# Juice_Rescue_v1_0.net
KiCad netlist of a schematic drawn in EAGLE
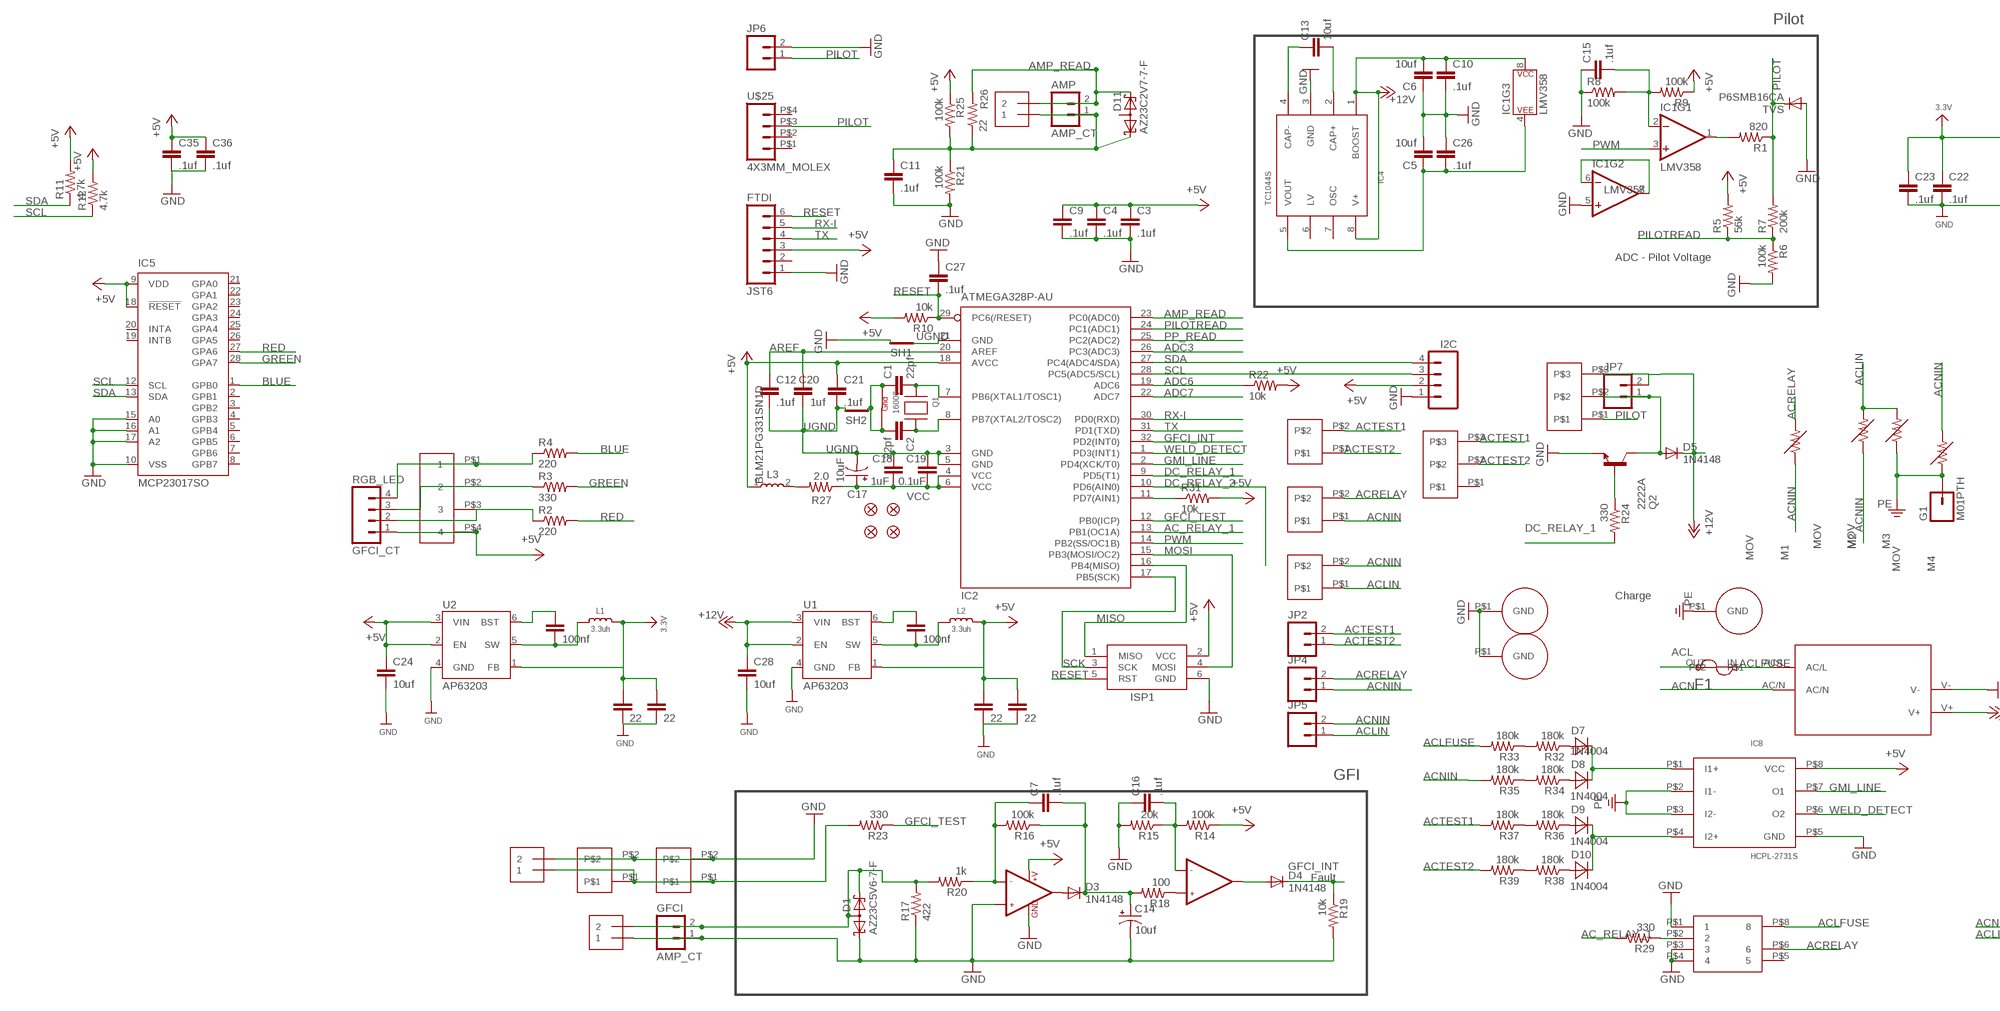
[diagram p0: schematic, sheet 1, part 1 of 2]
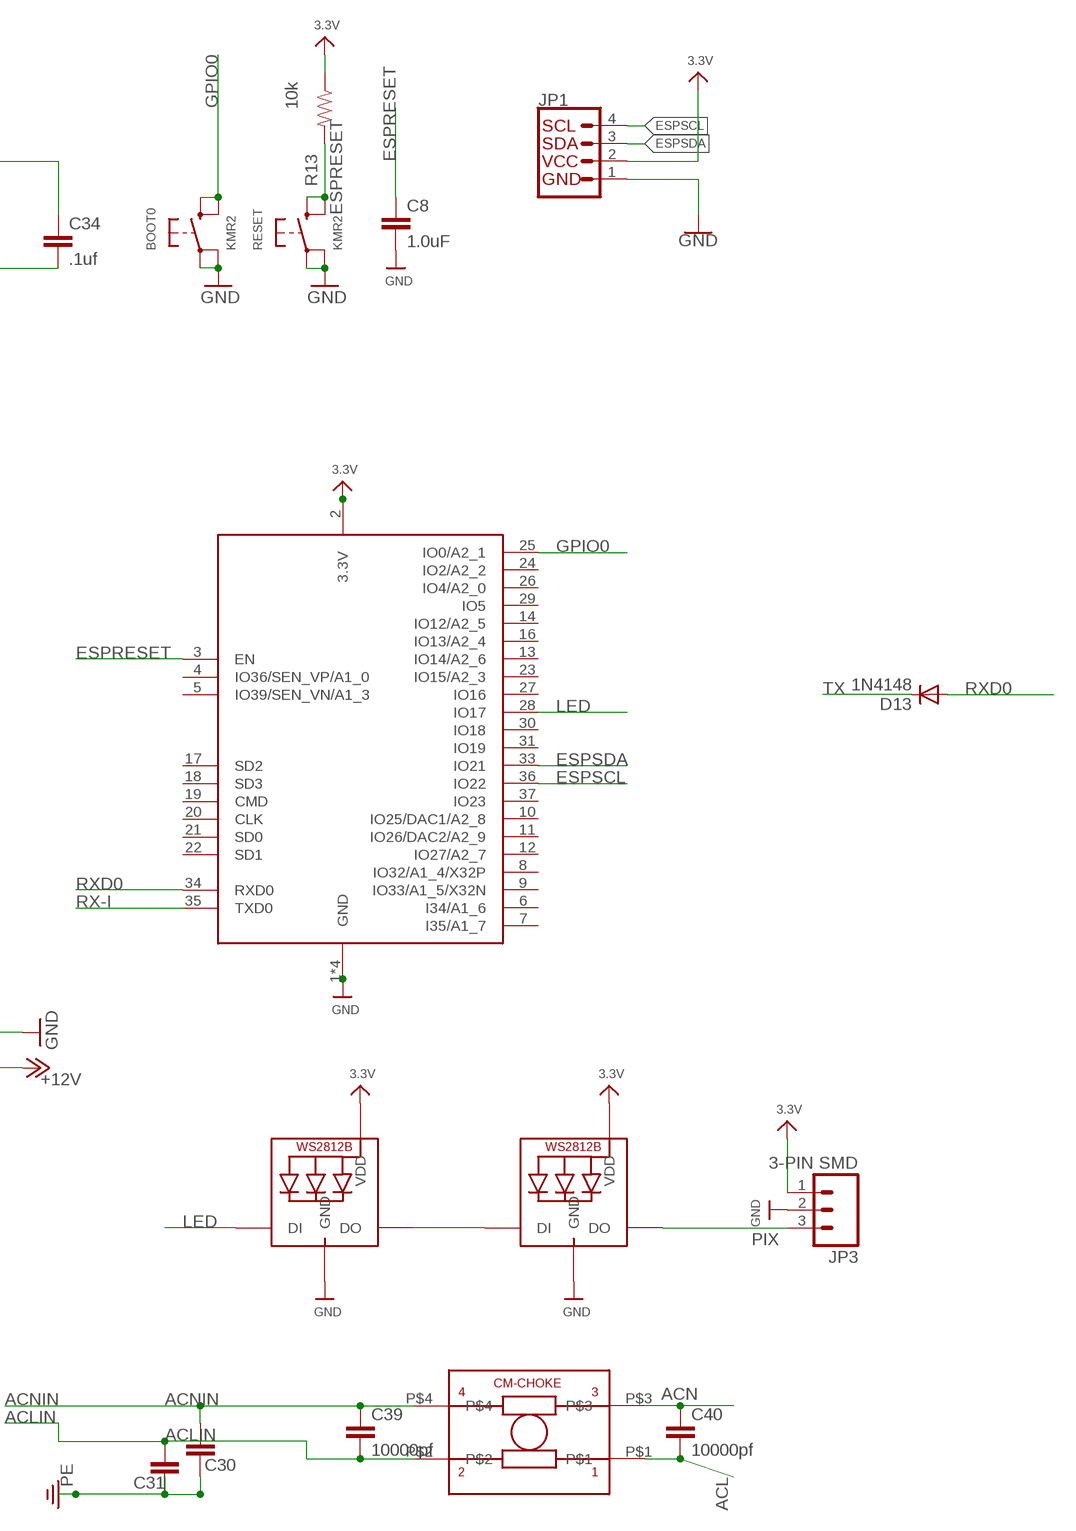
[diagram p1: schematic, sheet 1, part 2 of 2]

(export (version "E")
  (design (tool "Eeschema 10.0.6"))
  (components
    (comp (ref "AMP")
      (value "AMP_CT")
      (footprint "eagle-import:MOLEX_2")
      (libsource (lib "eagle-import") (part "MOLEX_2"))
    )
    (comp (ref "BOOT0")
      (value "KMR2")
      (footprint "eagle-import:BTN_KMR2_4.6X2.8")
      (libsource (lib "eagle-import") (part "SWITCH_TACT_SMT4.6X2.8"))
    )
    (comp (ref "C1")
      (value "22pf")
      (footprint "eagle-import:0805")
      (libsource (lib "eagle-import") (part "CAP0805"))
    )
    (comp (ref "C2")
      (value "22pf")
      (footprint "eagle-import:0805")
      (libsource (lib "eagle-import") (part "CAP0805"))
    )
    (comp (ref "C3")
      (value ".1uf")
      (footprint "eagle-import:0805")
      (libsource (lib "eagle-import") (part "CAP0805"))
    )
    (comp (ref "C4")
      (value ".1uf")
      (footprint "eagle-import:0805")
      (libsource (lib "eagle-import") (part "CAP0805"))
    )
    (comp (ref "C5")
      (value "10uf")
      (footprint "eagle-import:0805")
      (libsource (lib "eagle-import") (part "CAP0805"))
    )
    (comp (ref "C6")
      (value "10uf")
      (footprint "eagle-import:0805")
      (libsource (lib "eagle-import") (part "CAP0805"))
    )
    (comp (ref "C7")
      (value ".1uf")
      (footprint "eagle-import:0805")
      (libsource (lib "eagle-import") (part "CAP0805"))
    )
    (comp (ref "C8")
      (value "1.0uF")
      (footprint "eagle-import:0805")
      (libsource (lib "eagle-import") (part "1.0UF-0805-25V-(+80/-20%)"))
    )
    (comp (ref "C9")
      (value ".1uf")
      (footprint "eagle-import:0805")
      (libsource (lib "eagle-import") (part "CAP0805"))
    )
    (comp (ref "C10")
      (value ".1uf")
      (footprint "eagle-import:0805")
      (libsource (lib "eagle-import") (part "CAP0805"))
    )
    (comp (ref "C11")
      (value ".1uf")
      (footprint "eagle-import:0805")
      (libsource (lib "eagle-import") (part "CAP0805"))
    )
    (comp (ref "C12")
      (value ".1uf")
      (footprint "eagle-import:0805")
      (libsource (lib "eagle-import") (part "CAP0805"))
    )
    (comp (ref "C13")
      (value "10uf")
      (footprint "eagle-import:0805")
      (libsource (lib "eagle-import") (part "CAP0805"))
    )
    (comp (ref "C14")
      (value "10uf")
      (footprint "eagle-import:EIA3216")
      (libsource (lib "eagle-import") (part "CAP_POL1206"))
    )
    (comp (ref "C15")
      (value ".1uf")
      (footprint "eagle-import:0805")
      (libsource (lib "eagle-import") (part "CAP0805"))
    )
    (comp (ref "C16")
      (value ".1uf")
      (footprint "eagle-import:0805")
      (libsource (lib "eagle-import") (part "CAP0805"))
    )
    (comp (ref "C17")
      (value "10uF")
      (footprint "eagle-import:0603-POLAR")
      (libsource (lib "eagle-import") (part "10UF-POLAR-0603-6.3V-20%(TANT)"))
    )
    (comp (ref "C18")
      (value "1uF")
      (footprint "eagle-import:0805")
      (libsource (lib "eagle-import") (part "CAP0805"))
    )
    (comp (ref "C19")
      (value "0.1uF")
      (footprint "eagle-import:0805")
      (libsource (lib "eagle-import") (part "CAP0805"))
    )
    (comp (ref "C20")
      (value "1uf")
      (footprint "eagle-import:0805")
      (libsource (lib "eagle-import") (part "CAP0805"))
    )
    (comp (ref "C21")
      (value ".1uf")
      (footprint "eagle-import:0805")
      (libsource (lib "eagle-import") (part "CAP0805"))
    )
    (comp (ref "C22")
      (value ".1uf")
      (footprint "eagle-import:0805")
      (libsource (lib "eagle-import") (part "1.0UF-0805-25V-(+80/-20%)"))
    )
    (comp (ref "C23")
      (value ".1uf")
      (footprint "eagle-import:0805")
      (libsource (lib "eagle-import") (part "1.0UF-0805-25V-(+80/-20%)"))
    )
    (comp (ref "C24")
      (value "10uf")
      (footprint "eagle-import:0805")
      (libsource (lib "eagle-import") (part "1.0UF-0805-25V-(+80/-20%)"))
    )
    (comp (ref "C25")
      (value "22")
      (footprint "eagle-import:0805")
      (libsource (lib "eagle-import") (part "1.0UF-0805-25V-(+80/-20%)"))
    )
    (comp (ref "C26")
      (value ".1uf")
      (footprint "eagle-import:0805")
      (libsource (lib "eagle-import") (part "CAP0805"))
    )
    (comp (ref "C27")
      (value ".1uf")
      (footprint "eagle-import:0805")
      (libsource (lib "eagle-import") (part "CAP0805"))
    )
    (comp (ref "C28")
      (value "10uf")
      (footprint "eagle-import:0805")
      (libsource (lib "eagle-import") (part "1.0UF-0805-25V-(+80/-20%)"))
    )
    (comp (ref "C29")
      (value "22")
      (footprint "eagle-import:0805")
      (libsource (lib "eagle-import") (part "1.0UF-0805-25V-(+80/-20%)"))
    )
    (comp (ref "C30")
      (value "100nf")
      (footprint "eagle-import:0805")
      (libsource (lib "eagle-import") (part "1.0UF-0805-25V-(+80/-20%)"))
    )
    (comp (ref "C31")
      (value "22")
      (footprint "eagle-import:0805")
      (libsource (lib "eagle-import") (part "1.0UF-0805-25V-(+80/-20%)"))
    )
    (comp (ref "C32")
      (value "100nf")
      (footprint "eagle-import:0805")
      (libsource (lib "eagle-import") (part "1.0UF-0805-25V-(+80/-20%)"))
    )
    (comp (ref "C33")
      (value "22")
      (footprint "eagle-import:0805")
      (libsource (lib "eagle-import") (part "1.0UF-0805-25V-(+80/-20%)"))
    )
    (comp (ref "C34")
      (value ".1uf")
      (footprint "eagle-import:0805")
      (libsource (lib "eagle-import") (part "1.0UF-0805-25V-(+80/-20%)"))
    )
    (comp (ref "C35")
      (value ".1uf")
      (footprint "eagle-import:0805")
      (libsource (lib "eagle-import") (part "CAP0805"))
    )
    (comp (ref "C36")
      (value ".1uf")
      (footprint "eagle-import:0805")
      (libsource (lib "eagle-import") (part "CAP0805"))
    )
    (comp (ref "C37")
      (value "1000pf")
      (footprint "eagle-import:DK1E3EA")
      (libsource (lib "eagle-import") (part "DK1"))
    )
    (comp (ref "C38")
      (value "1000pf")
      (footprint "eagle-import:DK1E3EA")
      (libsource (lib "eagle-import") (part "DK1"))
    )
    (comp (ref "C39")
      (value "10000pf")
      (footprint "eagle-import:C7.5B4")
      (libsource (lib "eagle-import") (part "C7.5/4"))
    )
    (comp (ref "C40")
      (value "10000pf")
      (footprint "eagle-import:C7.5B4")
      (libsource (lib "eagle-import") (part "C7.5/4"))
    )
    (comp (ref "CMC")
      (value "RN214-0.3-02-47M")
      (footprint "eagle-import:RN214-0.3-02-47M")
      (libsource (lib "eagle-import") (part "RN214-0.3-02-47M"))
    )
    (comp (ref "D1")
      (value "AZ23C5V6-7-F")
      (footprint "eagle-import:SOT23")
      (libsource (lib "eagle-import") (part "BAS40-06"))
    )
    (comp (ref "D3")
      (value "1N4148")
      (footprint "eagle-import:SOD123")
      (libsource (lib "eagle-import") (part "DIODE-SOD123"))
    )
    (comp (ref "D4")
      (value "1N4148")
      (footprint "eagle-import:SOD123")
      (libsource (lib "eagle-import") (part "DIODE-SOD123"))
    )
    (comp (ref "D5")
      (value "1N4148")
      (footprint "eagle-import:SOD123")
      (libsource (lib "eagle-import") (part "DIODE-SOD123"))
    )
    (comp (ref "D7")
      (value "1N4004")
      (footprint "eagle-import:SMA")
      (libsource (lib "eagle-import") (part "MBRA340T3"))
    )
    (comp (ref "D8")
      (value "1N4004")
      (footprint "eagle-import:SMA")
      (libsource (lib "eagle-import") (part "MBRA340T3"))
    )
    (comp (ref "D9")
      (value "1N4004")
      (footprint "eagle-import:SMA")
      (libsource (lib "eagle-import") (part "MBRA340T3"))
    )
    (comp (ref "D10")
      (value "1N4004")
      (footprint "eagle-import:SMA")
      (libsource (lib "eagle-import") (part "MBRA340T3"))
    )
    (comp (ref "D11")
      (value "AZ23C2V7-7-F")
      (footprint "eagle-import:SOT23")
      (libsource (lib "eagle-import") (part "BAS40-06"))
    )
    (comp (ref "D13")
      (value "1N4148")
      (footprint "eagle-import:SOD123")
      (libsource (lib "eagle-import") (part "DIODE-SOD123"))
    )
    (comp (ref "F1")
      (value "BEL1.6AFUSE")
      (footprint "eagle-import:BELFUSE1A")
      (libsource (lib "eagle-import") (part "BEL1AFUSE"))
    )
    (comp (ref "FID1")
      (value "FIDUCIAL1X2.5")
      (footprint "eagle-import:FIDUCIAL-1X2.5")
      (libsource (lib "eagle-import") (part "FIDUCIAL1X2.5"))
    )
    (comp (ref "FID2")
      (value "FIDUCIAL1X2.5")
      (footprint "eagle-import:FIDUCIAL-1X2.5")
      (libsource (lib "eagle-import") (part "FIDUCIAL1X2.5"))
    )
    (comp (ref "FID3")
      (value "FIDUCIAL1X2.5")
      (footprint "eagle-import:FIDUCIAL-1X2.5")
      (libsource (lib "eagle-import") (part "FIDUCIAL1X2.5"))
    )
    (comp (ref "FID4")
      (value "FIDUCIAL1X2.5")
      (footprint "eagle-import:FIDUCIAL-1X2.5")
      (libsource (lib "eagle-import") (part "FIDUCIAL1X2.5"))
    )
    (comp (ref "FTDI")
      (value "JST6")
      (footprint "eagle-import:JST6")
      (libsource (lib "eagle-import") (part "JST6"))
    )
    (comp (ref "G1")
      (value "M01PTH")
      (footprint "eagle-import:1X01")
      (libsource (lib "eagle-import") (part "M01PTH"))
    )
    (comp (ref "GFCI")
      (value "AMP_CT")
      (footprint "eagle-import:MOLEX_2")
      (libsource (lib "eagle-import") (part "MOLEX_2"))
    )
    (comp (ref "I2C")
      (value "M04JST-PTH-VERT")
      (footprint "eagle-import:JST-4-PTH-VERT")
      (libsource (lib "eagle-import") (part "M04JST-PTH-VERT"))
    )
    (comp (ref "IC1")
      (value "LMV358")
      (footprint "eagle-import:SO08")
      (libsource (lib "eagle-import") (part "LMV358SOIC"))
    )
    (comp (ref "IC2")
      (value "ATMEGA328P-AU")
      (footprint "eagle-import:TQFP32-08")
      (fields (field (name "MPN") "ATMEGA8-16AU"))
      (libsource (lib "eagle-import") (part "MEGA8-AI"))
    )
    (comp (ref "IC3")
      (value "LM358")
      (footprint "eagle-import:SO08")
      (libsource (lib "eagle-import") (part "LMV358"))
    )
    (comp (ref "IC4")
      (value "TC1044S")
      (footprint "eagle-import:SO-8")
      (libsource (lib "eagle-import") (part "TC1044S"))
    )
    (comp (ref "IC5")
      (value "MCP23017SO")
      (footprint "eagle-import:SO28W")
      (libsource (lib "eagle-import") (part "MCP23017SO"))
    )
    (comp (ref "IC7")
      (value "AQH2223")
      (footprint "eagle-import:SIL8")
      (libsource (lib "eagle-import") (part "AQH2223"))
    )
    (comp (ref "IC8")
      (value "HCPL-2731S")
      (footprint "eagle-import:SIL8-2")
      (libsource (lib "eagle-import") (part "HCPL-2731S"))
    )
    (comp (ref "ISP1")
      (value "ISP1")
      (footprint "eagle-import:AVRISP")
      (libsource (lib "eagle-import") (part "AVRISP-6"))
    )
    (comp (ref "J1")
      (value "1X2-3.5MM")
      (footprint "eagle-import:1X2-3.5MM")
      (libsource (lib "eagle-import") (part "1X2-3.5MM"))
    )
    (comp (ref "J2")
      (value "1X2-3.5MM")
      (footprint "eagle-import:1X2-3.5MM")
      (libsource (lib "eagle-import") (part "1X2-3.5MM"))
    )
    (comp (ref "J3")
      (value "1X2-3.5MM")
      (footprint "eagle-import:1X2-3.5MM")
      (libsource (lib "eagle-import") (part "1X2-3.5MM"))
    )
    (comp (ref "JP1")
      (value "QWIIC_CONNECTORJS-1MM")
      (footprint "eagle-import:JST04_1MM_RA")
      (libsource (lib "eagle-import") (part "QWIIC_CONNECTORJS-1MM"))
    )
    (comp (ref "JP2")
      (value "M025MM")
      (footprint "eagle-import:SCREWTERMINAL-5MM-2")
      (libsource (lib "eagle-import") (part "M025MM"))
    )
    (comp (ref "JP3")
      (value "3-PIN SMD")
      (footprint "eagle-import:JST-3-SMD")
      (libsource (lib "eagle-import") (part "M03JST-SMD"))
    )
    (comp (ref "JP4")
      (value "M025MM")
      (footprint "eagle-import:SCREWTERMINAL-5MM-2")
      (libsource (lib "eagle-import") (part "M025MM"))
    )
    (comp (ref "JP5")
      (value "M025MM")
      (footprint "eagle-import:SCREWTERMINAL-5MM-2")
      (libsource (lib "eagle-import") (part "M025MM"))
    )
    (comp (ref "JP6")
      (value "M025MM")
      (footprint "eagle-import:SCREWTERMINAL-5MM-2")
      (libsource (lib "eagle-import") (part "M025MM"))
    )
    (comp (ref "JP7")
      (value "M025MM")
      (footprint "eagle-import:SCREWTERMINAL-5MM-2")
      (libsource (lib "eagle-import") (part "M025MM"))
    )
    (comp (ref "L1")
      (value "3.3uh")
      (footprint "eagle-import:MICROBUILDER_INDUCTOR_5X5MM_NR5040_NOTHERMALS")
      (libsource (lib "eagle-import") (part "MICROBUILDER_INDUCTORNR5040"))
    )
    (comp (ref "L2")
      (value "3.3uh")
      (footprint "eagle-import:MICROBUILDER_INDUCTOR_5X5MM_NR5040_NOTHERMALS")
      (libsource (lib "eagle-import") (part "MICROBUILDER_INDUCTORNR5040"))
    )
    (comp (ref "L3")
      (value "BLM21PG331SN1D")
      (footprint "eagle-import:INDC2012X87")
      (fields (field (name "MF") "Murata"))
      (libsource (lib "eagle-import") (part "BLM21PG331SN1D"))
    )
    (comp (ref "LED1")
      (value "WS2812B3535")
      (footprint "eagle-import:LED3535")
      (libsource (lib "eagle-import") (part "WS2812B3535"))
    )
    (comp (ref "LED2")
      (value "WS2812B3535")
      (footprint "eagle-import:LED3535")
      (libsource (lib "eagle-import") (part "WS2812B3535"))
    )
    (comp (ref "M1")
      (value "MOV")
      (footprint "eagle-import:MOV")
      (libsource (lib "eagle-import") (part "MOV"))
    )
    (comp (ref "M2")
      (value "MOV")
      (footprint "eagle-import:MOV")
      (libsource (lib "eagle-import") (part "MOV"))
    )
    (comp (ref "M3")
      (value "MOV")
      (footprint "eagle-import:MOV")
      (libsource (lib "eagle-import") (part "MOV"))
    )
    (comp (ref "M4")
      (value "MOV")
      (footprint "eagle-import:MOV")
      (libsource (lib "eagle-import") (part "MOV"))
    )
    (comp (ref "PS1")
      (value "IRM-10-5")
      (footprint "eagle-import:IRM-10-5")
      (libsource (lib "eagle-import") (part "IRM-10-5"))
    )
    (comp (ref "Q1")
      (value "16000")
      (footprint "eagle-import:NX3225")
      (libsource (lib "eagle-import") (part "XTAL-4-3225"))
    )
    (comp (ref "Q2")
      (value "2222A")
      (footprint "eagle-import:SOT23")
      (libsource (lib "eagle-import") (part "BCX70SMD"))
    )
    (comp (ref "R1")
      (value "820")
      (footprint "eagle-import:0805")
      (libsource (lib "eagle-import") (part "RESISTOR0805-RES"))
    )
    (comp (ref "R2")
      (value "220")
      (footprint "eagle-import:0805")
      (libsource (lib "eagle-import") (part "RESISTOR0805-RES"))
    )
    (comp (ref "R3")
      (value "330")
      (footprint "eagle-import:0805")
      (libsource (lib "eagle-import") (part "RESISTOR0805-RES"))
    )
    (comp (ref "R4")
      (value "220")
      (footprint "eagle-import:0805")
      (libsource (lib "eagle-import") (part "RESISTOR0805-RES"))
    )
    (comp (ref "R5")
      (value "56k")
      (footprint "eagle-import:0805")
      (libsource (lib "eagle-import") (part "RESISTOR0805-RES"))
    )
    (comp (ref "R6")
      (value "100k")
      (footprint "eagle-import:0805")
      (libsource (lib "eagle-import") (part "RESISTOR0805-RES"))
    )
    (comp (ref "R7")
      (value "200k")
      (footprint "eagle-import:0805")
      (libsource (lib "eagle-import") (part "RESISTOR0805-RES"))
    )
    (comp (ref "R8")
      (value "100k")
      (footprint "eagle-import:0805")
      (libsource (lib "eagle-import") (part "RESISTOR0805-RES"))
    )
    (comp (ref "R9")
      (value "100k")
      (footprint "eagle-import:0805")
      (libsource (lib "eagle-import") (part "RESISTOR0805-RES"))
    )
    (comp (ref "R10")
      (value "10k")
      (footprint "eagle-import:0805")
      (libsource (lib "eagle-import") (part "RESISTOR0805-RES"))
    )
    (comp (ref "R11")
      (value "4.7k")
      (footprint "eagle-import:0805")
      (libsource (lib "eagle-import") (part "RESISTOR0805-RES"))
    )
    (comp (ref "R12")
      (value "4.7k")
      (footprint "eagle-import:0805")
      (libsource (lib "eagle-import") (part "RESISTOR0805-RES"))
    )
    (comp (ref "R13")
      (value "10k")
      (footprint "eagle-import:0805")
      (libsource (lib "eagle-import") (part "RESISTOR0805"))
    )
    (comp (ref "R14")
      (value "100k")
      (footprint "eagle-import:0805")
      (libsource (lib "eagle-import") (part "RESISTOR0805-RES"))
    )
    (comp (ref "R15")
      (value "20k")
      (footprint "eagle-import:0805")
      (libsource (lib "eagle-import") (part "RESISTOR0805-RES"))
    )
    (comp (ref "R16")
      (value "100k")
      (footprint "eagle-import:0805")
      (libsource (lib "eagle-import") (part "RESISTOR0805-RES"))
    )
    (comp (ref "R17")
      (value "422")
      (footprint "eagle-import:0805")
      (libsource (lib "eagle-import") (part "RESISTOR0805-RES"))
    )
    (comp (ref "R18")
      (value "100")
      (footprint "eagle-import:0805")
      (libsource (lib "eagle-import") (part "RESISTOR0805-RES"))
    )
    (comp (ref "R19")
      (value "10k")
      (footprint "eagle-import:0805")
      (libsource (lib "eagle-import") (part "RESISTOR0805-RES"))
    )
    (comp (ref "R20")
      (value "1k")
      (footprint "eagle-import:0805")
      (libsource (lib "eagle-import") (part "RESISTOR0805-RES"))
    )
    (comp (ref "R21")
      (value "100k")
      (footprint "eagle-import:0805")
      (libsource (lib "eagle-import") (part "RESISTOR0805-RES"))
    )
    (comp (ref "R22")
      (value "10k")
      (footprint "eagle-import:0805")
      (libsource (lib "eagle-import") (part "RESISTOR0805-RES"))
    )
    (comp (ref "R23")
      (value "330")
      (footprint "eagle-import:0805")
      (libsource (lib "eagle-import") (part "RESISTOR0805-RES"))
    )
    (comp (ref "R24")
      (value "330")
      (footprint "eagle-import:0805")
      (libsource (lib "eagle-import") (part "RESISTOR0805-RES"))
    )
    (comp (ref "R25")
      (value "100k")
      (footprint "eagle-import:0805")
      (libsource (lib "eagle-import") (part "RESISTOR0805-RES"))
    )
    (comp (ref "R26")
      (value "22")
      (footprint "eagle-import:R1206")
      (libsource (lib "eagle-import") (part "R-US_R1206"))
    )
    (comp (ref "R27")
      (value "2.0")
      (footprint "eagle-import:0805")
      (libsource (lib "eagle-import") (part "RESISTOR0805-RES"))
    )
    (comp (ref "R29")
      (value "330")
      (footprint "eagle-import:0805")
      (libsource (lib "eagle-import") (part "RESISTOR0805-RES"))
    )
    (comp (ref "R31")
      (value "10k")
      (footprint "eagle-import:0805")
      (libsource (lib "eagle-import") (part "RESISTOR0805-RES"))
    )
    (comp (ref "R32")
      (value "180k")
      (footprint "eagle-import:1210")
      (libsource (lib "eagle-import") (part "0.1OHM-1/2W-1%(1210)"))
    )
    (comp (ref "R33")
      (value "180k")
      (footprint "eagle-import:1210")
      (libsource (lib "eagle-import") (part "0.1OHM-1/2W-1%(1210)"))
    )
    (comp (ref "R34")
      (value "180k")
      (footprint "eagle-import:1210")
      (libsource (lib "eagle-import") (part "0.1OHM-1/2W-1%(1210)"))
    )
    (comp (ref "R35")
      (value "180k")
      (footprint "eagle-import:1210")
      (libsource (lib "eagle-import") (part "0.1OHM-1/2W-1%(1210)"))
    )
    (comp (ref "R36")
      (value "180k")
      (footprint "eagle-import:1210")
      (libsource (lib "eagle-import") (part "0.1OHM-1/2W-1%(1210)"))
    )
    (comp (ref "R37")
      (value "180k")
      (footprint "eagle-import:1210")
      (libsource (lib "eagle-import") (part "0.1OHM-1/2W-1%(1210)"))
    )
    (comp (ref "R38")
      (value "180k")
      (footprint "eagle-import:1210")
      (libsource (lib "eagle-import") (part "0.1OHM-1/2W-1%(1210)"))
    )
    (comp (ref "R39")
      (value "180k")
      (footprint "eagle-import:1210")
      (libsource (lib "eagle-import") (part "0.1OHM-1/2W-1%(1210)"))
    )
    (comp (ref "RESET")
      (value "KMR2")
      (footprint "eagle-import:BTN_KMR2_4.6X2.8")
      (libsource (lib "eagle-import") (part "SWITCH_TACT_SMT4.6X2.8"))
    )
    (comp (ref "RGB_LED")
      (value "GFCI_CT")
      (footprint "eagle-import:GFCI_4")
      (libsource (lib "eagle-import") (part "GFCI_4"))
    )
    (comp (ref "SH1")
      (value "SHORT-HT5")
      (footprint "eagle-import:SHORT_TOP-50")
      (libsource (lib "eagle-import") (part "SHORT-HT5"))
    )
    (comp (ref "SH2")
      (value "SHORT-HT5")
      (footprint "eagle-import:SHORT_TOP-50")
      (libsource (lib "eagle-import") (part "SHORT-HT5"))
    )
    (comp (ref "TVS")
      (value "P6SMB16CA")
      (footprint "eagle-import:SMB")
      (libsource (lib "eagle-import") (part "DIODE-SMB"))
    )
    (comp (ref "U$1")
      (value "AMPAC")
      (footprint "eagle-import:AMPAC")
      (libsource (lib "eagle-import") (part "AMPAC"))
    )
    (comp (ref "U$3")
      (value "HOLE")
      (footprint "eagle-import:HOLE")
      (libsource (lib "eagle-import") (part "HOLE"))
    )
    (comp (ref "U$8")
      (value "AMPAC")
      (footprint "eagle-import:AMPAC")
      (libsource (lib "eagle-import") (part "AMPAC"))
    )
    (comp (ref "U$9")
      (value "HOLE")
      (footprint "eagle-import:HOLE")
      (libsource (lib "eagle-import") (part "HOLE"))
    )
    (comp (ref "U$14")
      (value "AMPAC")
      (footprint "eagle-import:AMPAC")
      (libsource (lib "eagle-import") (part "AMPAC"))
    )
    (comp (ref "U$17")
      (value "AMPAC")
      (footprint "eagle-import:AMPAC")
      (libsource (lib "eagle-import") (part "AMPAC"))
    )
    (comp (ref "U$20")
      (value "AMP3POS")
      (footprint "eagle-import:AMP3POS")
      (libsource (lib "eagle-import") (part "AMP3POS"))
    )
    (comp (ref "U$22")
      (value "AMPAC3P")
      (footprint "eagle-import:ACAMP3P")
      (libsource (lib "eagle-import") (part "AMPAC3P"))
    )
    (comp (ref "U$23")
      (value "2X4MM")
      (footprint "eagle-import:2X4MM")
      (libsource (lib "eagle-import") (part "2X4MM"))
    )
    (comp (ref "U$24")
      (value "4X1MMRIBBON")
      (footprint "eagle-import:4X1MMRIBBON")
      (libsource (lib "eagle-import") (part "4X1MMRIBBON"))
    )
    (comp (ref "U$25")
      (value "4X3MM_MOLEX")
      (footprint "eagle-import:4X3MM_MOLEX")
      (libsource (lib "eagle-import") (part "4X3MM_MOLEX"))
    )
    (comp (ref "U$27")
      (value "HOLE")
      (footprint "eagle-import:HOLE")
      (libsource (lib "eagle-import") (part "HOLE"))
    )
    (comp (ref "U1")
      (value "AP63203")
      (footprint "eagle-import:SOT23-6")
      (libsource (lib "eagle-import") (part "AP63203"))
    )
    (comp (ref "U2")
      (value "AP63203")
      (footprint "eagle-import:SOT23-6")
      (libsource (lib "eagle-import") (part "AP63203"))
    )
    (comp (ref "X2")
      (value "ESP32-WROOM-32")
      (footprint "eagle-import:WROOM32_SKINNY")
      (libsource (lib "eagle-import") (part "ESP32_WROOM32_SKINNY"))
    )
  )
  (nets
    (net (code "1") (name "+5V") (class "Default")
      (node (ref "C21") (pin "1") (pinfunction "1_1") (pintype "passive"))
      (node (ref "C24") (pin "1") (pinfunction "1_1") (pintype "passive"))
      (node (ref "C29") (pin "1") (pinfunction "1_1") (pintype "passive"))
      (node (ref "C3") (pin "1") (pinfunction "1_1") (pintype "passive"))
      (node (ref "C33") (pin "1") (pinfunction "1_1") (pintype "passive"))
      (node (ref "C35") (pin "1") (pinfunction "1_1") (pintype "passive"))
      (node (ref "C36") (pin "1") (pinfunction "1_1") (pintype "passive"))
      (node (ref "C4") (pin "1") (pinfunction "1_1") (pintype "passive"))
      (node (ref "C9") (pin "1") (pinfunction "1_1") (pintype "passive"))
      (node (ref "FTDI") (pin "3") (pinfunction "3_3") (pintype "passive"))
      (node (ref "I2C") (pin "2") (pinfunction "2_2") (pintype "passive"))
      (node (ref "IC2") (pin "18") (pinfunction "AVCC_18") (pintype "power_in"))
      (node (ref "IC3") (pin "8") (pinfunction "+V_8") (pintype "power_in"))
      (node (ref "IC5") (pin "18") (pinfunction "~{RESET}_18") (pintype "input"))
      (node (ref "IC5") (pin "9") (pinfunction "VDD_9") (pintype "power_in"))
      (node (ref "IC8") (pin "P$8") (pinfunction "VCC_P$8") (pintype "bidirectional"))
      (node (ref "ISP1") (pin "2") (pinfunction "VCC_2") (pintype "power_in"))
      (node (ref "L2") (pin "P$2") (pinfunction "2_P$2") (pintype "passive"))
      (node (ref "L3") (pin "1") (pinfunction "1_1") (pintype "passive"))
      (node (ref "R10") (pin "2") (pinfunction "2_2") (pintype "passive"))
      (node (ref "R11") (pin "2") (pinfunction "2_2") (pintype "passive"))
      (node (ref "R12") (pin "2") (pinfunction "2_2") (pintype "passive"))
      (node (ref "R14") (pin "1") (pinfunction "1_1") (pintype "passive"))
      (node (ref "R22") (pin "2") (pinfunction "2_2") (pintype "passive"))
      (node (ref "R25") (pin "1") (pinfunction "1_1") (pintype "passive"))
      (node (ref "R31") (pin "2") (pinfunction "2_2") (pintype "passive"))
      (node (ref "R5") (pin "2") (pinfunction "2_2") (pintype "passive"))
      (node (ref "R9") (pin "1") (pinfunction "1_1") (pintype "passive"))
      (node (ref "RGB_LED") (pin "1") (pinfunction "1_1") (pintype "passive"))
      (node (ref "U$24") (pin "P$4") (pinfunction "4_P$4") (pintype "bidirectional"))
      (node (ref "U1") (pin "1") (pinfunction "FB_1") (pintype "bidirectional"))
      (node (ref "U2") (pin "2") (pinfunction "EN_2") (pintype "bidirectional"))
      (node (ref "U2") (pin "3") (pinfunction "VIN_3") (pintype "bidirectional"))
    )
    (net (code "2") (name "+12V") (class "Default")
      (node (ref "C10") (pin "1") (pinfunction "1_1") (pintype "passive"))
      (node (ref "C28") (pin "1") (pinfunction "1_1") (pintype "passive"))
      (node (ref "C6") (pin "2") (pinfunction "2_2") (pintype "passive"))
      (node (ref "D5") (pin "C") (pinfunction "C_C") (pintype "passive"))
      (node (ref "IC1") (pin "8") (pinfunction "P$V+_8") (pintype "bidirectional"))
      (node (ref "IC4") (pin "1") (pinfunction "BOOST_1") (pintype "bidirectional"))
      (node (ref "IC4") (pin "8") (pinfunction "V+_8") (pintype "bidirectional"))
      (node (ref "JP7") (pin "2") (pinfunction "2_2") (pintype "passive"))
      (node (ref "PS1") (pin "V+") (pinfunction "V+_V+") (pintype "bidirectional"))
      (node (ref "U$20") (pin "P$3") (pinfunction "P$3_P$3") (pintype "bidirectional"))
      (node (ref "U1") (pin "2") (pinfunction "EN_2") (pintype "bidirectional"))
      (node (ref "U1") (pin "3") (pinfunction "VIN_3") (pintype "bidirectional"))
    )
    (net (code "3") (name "/ACL") (class "Default")
      (node (ref "C40") (pin "2") (pinfunction "2_2") (pintype "passive"))
      (node (ref "CMC") (pin "P$1") (pinfunction "P$1_P$1") (pintype "bidirectional"))
      (node (ref "F1") (pin "OUT") (pinfunction "P$1_OUT") (pintype "bidirectional"))
    )
    (net (code "4") (name "/ACLFUSE") (class "Default")
      (node (ref "F1") (pin "IN") (pinfunction "P$2_IN") (pintype "bidirectional"))
      (node (ref "IC7") (pin "P$8") (pinfunction "8_P$8") (pintype "bidirectional"))
      (node (ref "PS1") (pin "AC/L") (pinfunction "AC/L_AC/L") (pintype "bidirectional"))
      (node (ref "R33") (pin "2") (pinfunction "2_2") (pintype "passive"))
    )
    (net (code "5") (name "/ACLIN") (class "Default")
      (node (ref "C38") (pin "P$2") (pinfunction "2_P$2") (pintype "passive"))
      (node (ref "C39") (pin "2") (pinfunction "2_2") (pintype "passive"))
      (node (ref "CMC") (pin "P$2") (pinfunction "P$2_P$2") (pintype "bidirectional"))
      (node (ref "JP5") (pin "1") (pinfunction "1_1") (pintype "passive"))
      (node (ref "M2") (pin "P$2") (pinfunction "2_P$2") (pintype "passive"))
      (node (ref "M3") (pin "P$2") (pinfunction "2_P$2") (pintype "passive"))
      (node (ref "U$1") (pin "P$1") (pinfunction "P$1_P$1") (pintype "bidirectional"))
    )
    (net (code "6") (name "/ACN") (class "Default")
      (node (ref "C40") (pin "1") (pinfunction "1_1") (pintype "passive"))
      (node (ref "CMC") (pin "P$3") (pinfunction "P$3_P$3") (pintype "bidirectional"))
      (node (ref "PS1") (pin "AC/N") (pinfunction "AC/N_AC/N") (pintype "bidirectional"))
    )
    (net (code "7") (name "/ACNIN") (class "Default")
      (node (ref "C37") (pin "P$2") (pinfunction "2_P$2") (pintype "passive"))
      (node (ref "C39") (pin "1") (pinfunction "1_1") (pintype "passive"))
      (node (ref "CMC") (pin "P$4") (pinfunction "P$4_P$4") (pintype "bidirectional"))
      (node (ref "JP4") (pin "1") (pinfunction "1_1") (pintype "passive"))
      (node (ref "JP5") (pin "2") (pinfunction "2_2") (pintype "passive"))
      (node (ref "M1") (pin "P$1") (pinfunction "1_P$1") (pintype "passive"))
      (node (ref "M2") (pin "P$1") (pinfunction "1_P$1") (pintype "passive"))
      (node (ref "M4") (pin "P$2") (pinfunction "2_P$2") (pintype "passive"))
      (node (ref "R35") (pin "2") (pinfunction "2_2") (pintype "passive"))
      (node (ref "U$1") (pin "P$2") (pinfunction "P$2_P$2") (pintype "bidirectional"))
      (node (ref "U$8") (pin "P$1") (pinfunction "P$1_P$1") (pintype "bidirectional"))
    )
    (net (code "8") (name "/ACRELAY") (class "Default")
      (node (ref "IC7") (pin "P$6") (pinfunction "6_P$6") (pintype "bidirectional"))
      (node (ref "JP4") (pin "2") (pinfunction "2_2") (pintype "passive"))
      (node (ref "M1") (pin "P$2") (pinfunction "2_P$2") (pintype "passive"))
      (node (ref "U$8") (pin "P$2") (pinfunction "P$2_P$2") (pintype "bidirectional"))
    )
    (net (code "9") (name "/ACTEST1") (class "Default")
      (node (ref "JP2") (pin "2") (pinfunction "2_2") (pintype "passive"))
      (node (ref "R37") (pin "2") (pinfunction "2_2") (pintype "passive"))
      (node (ref "U$14") (pin "P$2") (pinfunction "P$2_P$2") (pintype "bidirectional"))
      (node (ref "U$22") (pin "P$3") (pinfunction "P$3_P$3") (pintype "bidirectional"))
    )
    (net (code "10") (name "/ACTEST2") (class "Default")
      (node (ref "JP2") (pin "1") (pinfunction "1_1") (pintype "passive"))
      (node (ref "R39") (pin "2") (pinfunction "2_2") (pintype "passive"))
      (node (ref "U$14") (pin "P$1") (pinfunction "P$1_P$1") (pintype "bidirectional"))
      (node (ref "U$22") (pin "P$2") (pinfunction "P$2_P$2") (pintype "bidirectional"))
    )
    (net (code "11") (name "/AC_RELAY_1") (class "Default")
      (node (ref "IC2") (pin "13") (pinfunction "PB1(OC1A)_13") (pintype "bidirectional"))
      (node (ref "R29") (pin "2") (pinfunction "2_2") (pintype "passive"))
    )
    (net (code "12") (name "/ADC3") (class "Default")
      (node (ref "IC2") (pin "26") (pinfunction "PC3(ADC3)_26") (pintype "bidirectional"))
    )
    (net (code "13") (name "/ADC6") (class "Default")
      (node (ref "IC2") (pin "19") (pinfunction "ADC6_19") (pintype "bidirectional"))
      (node (ref "R22") (pin "1") (pinfunction "1_1") (pintype "passive"))
    )
    (net (code "14") (name "/ADC7") (class "Default")
      (node (ref "IC2") (pin "22") (pinfunction "ADC7_22") (pintype "bidirectional"))
    )
    (net (code "15") (name "/AMP_READ") (class "Default")
      (node (ref "AMP") (pin "2") (pinfunction "2_2") (pintype "passive"))
      (node (ref "D11") (pin "2") (pinfunction "K2_2") (pintype "passive"))
      (node (ref "IC2") (pin "23") (pinfunction "PC0(ADC0)_23") (pintype "bidirectional"))
      (node (ref "J3") (pin "2") (pinfunction "2_2") (pintype "passive"))
      (node (ref "R26") (pin "2") (pinfunction "2_2") (pintype "passive"))
    )
    (net (code "16") (name "/AREF") (class "Default")
      (node (ref "C12") (pin "1") (pinfunction "1_1") (pintype "passive"))
      (node (ref "C20") (pin "1") (pinfunction "1_1") (pintype "passive"))
      (node (ref "IC2") (pin "20") (pinfunction "AREF_20") (pintype "passive"))
    )
    (net (code "17") (name "/BLUE") (class "Default")
      (node (ref "IC5") (pin "1") (pinfunction "GPB0_1") (pintype "bidirectional"))
      (node (ref "R4") (pin "2") (pinfunction "2_2") (pintype "passive"))
    )
    (net (code "18") (name "/DC_RELAY_1") (class "Default")
      (node (ref "IC2") (pin "9") (pinfunction "PD5(T1)_9") (pintype "bidirectional"))
      (node (ref "R24") (pin "2") (pinfunction "2_2") (pintype "passive"))
    )
    (net (code "19") (name "/DC_RELAY_2") (class "Default")
      (node (ref "IC2") (pin "10") (pinfunction "PD6(AIN0)_10") (pintype "bidirectional"))
    )
    (net (code "20") (name "/ESPRESET") (class "Default")
      (node (ref "C8") (pin "1") (pinfunction "1_1") (pintype "passive"))
      (node (ref "R13") (pin "2") (pinfunction "2_2") (pintype "passive"))
      (node (ref "RESET") (pin "B") (pinfunction "S_B") (pintype "passive"))
      (node (ref "RESET") (pin "B'") (pinfunction "S1_B'") (pintype "passive"))
      (node (ref "X2") (pin "3") (pinfunction "EN_3") (pintype "input"))
    )
    (net (code "21") (name "/GFCI_INT") (class "Default")
      (node (ref "D4") (pin "C") (pinfunction "C_C") (pintype "passive"))
      (node (ref "IC2") (pin "32") (pinfunction "PD2(INT0)_32") (pintype "bidirectional"))
      (node (ref "R19") (pin "1") (pinfunction "1_1") (pintype "passive"))
    )
    (net (code "22") (name "/GFCI_TEST") (class "Default")
      (node (ref "IC2") (pin "12") (pinfunction "PB0(ICP)_12") (pintype "bidirectional"))
      (node (ref "R23") (pin "1") (pinfunction "1_1") (pintype "passive"))
    )
    (net (code "23") (name "/GMI_LINE") (class "Default")
      (node (ref "IC2") (pin "2") (pinfunction "PD4(XCK/T0)_2") (pintype "bidirectional"))
      (node (ref "IC8") (pin "P$7") (pinfunction "O1_P$7") (pintype "bidirectional"))
    )
    (net (code "24") (name "/GPIO0") (class "Default")
      (node (ref "BOOT0") (pin "B") (pinfunction "S_B") (pintype "passive"))
      (node (ref "BOOT0") (pin "B'") (pinfunction "S1_B'") (pintype "passive"))
      (node (ref "X2") (pin "25") (pinfunction "IO0/A2_1_25") (pintype "bidirectional"))
    )
    (net (code "25") (name "/GREEN") (class "Default")
      (node (ref "IC5") (pin "28") (pinfunction "GPA7_28") (pintype "bidirectional"))
      (node (ref "R3") (pin "2") (pinfunction "2_2") (pintype "passive"))
    )
    (net (code "26") (name "/LED") (class "Default")
      (node (ref "LED1") (pin "1") (pinfunction "DI_1") (pintype "input"))
      (node (ref "X2") (pin "28") (pinfunction "IO17_28") (pintype "bidirectional"))
    )
    (net (code "27") (name "/MISO") (class "Default")
      (node (ref "IC2") (pin "16") (pinfunction "PB4(MISO)_16") (pintype "bidirectional"))
      (node (ref "ISP1") (pin "1") (pinfunction "MISO_1") (pintype "input"))
    )
    (net (code "28") (name "/MOSI") (class "Default")
      (node (ref "IC2") (pin "15") (pinfunction "PB3(MOSI/OC2)_15") (pintype "bidirectional"))
      (node (ref "ISP1") (pin "4") (pinfunction "MOSI_4") (pintype "output"))
    )
    (net (code "29") (name "/PILOT") (class "Default")
      (node (ref "JP6") (pin "1") (pinfunction "1_1") (pintype "passive"))
      (node (ref "R1") (pin "1") (pinfunction "1_1") (pintype "passive"))
      (node (ref "R7") (pin "2") (pinfunction "2_2") (pintype "passive"))
      (node (ref "TVS") (pin "C") (pinfunction "C_C") (pintype "passive"))
      (node (ref "U$20") (pin "P$1") (pinfunction "P$1_P$1") (pintype "bidirectional"))
      (node (ref "U$25") (pin "P$3") (pinfunction "3_P$3") (pintype "passive"))
    )
    (net (code "30") (name "/PILOTREAD") (class "Default")
      (node (ref "IC2") (pin "24") (pinfunction "PC1(ADC1)_24") (pintype "bidirectional"))
      (node (ref "R5") (pin "1") (pinfunction "1_1") (pintype "passive"))
      (node (ref "R6") (pin "1") (pinfunction "1_1") (pintype "passive"))
      (node (ref "R7") (pin "1") (pinfunction "1_1") (pintype "passive"))
    )
    (net (code "31") (name "/PIX") (class "Default")
      (node (ref "JP3") (pin "3") (pinfunction "3_3") (pintype "passive"))
      (node (ref "LED2") (pin "3") (pinfunction "DO_3") (pintype "output"))
    )
    (net (code "32") (name "/PP_READ") (class "Default")
      (node (ref "IC2") (pin "25") (pinfunction "PC2(ADC2)_25") (pintype "bidirectional"))
    )
    (net (code "33") (name "/PWM") (class "Default")
      (node (ref "IC1") (pin "3") (pinfunction "+IN_3") (pintype "input"))
      (node (ref "IC2") (pin "14") (pinfunction "PB2(SS/OC1B)_14") (pintype "bidirectional"))
    )
    (net (code "34") (name "/RED") (class "Default")
      (node (ref "IC5") (pin "27") (pinfunction "GPA6_27") (pintype "bidirectional"))
      (node (ref "R2") (pin "2") (pinfunction "2_2") (pintype "passive"))
    )
    (net (code "35") (name "/RESET") (class "Default")
      (node (ref "C27") (pin "2") (pinfunction "2_2") (pintype "passive"))
      (node (ref "FTDI") (pin "6") (pinfunction "6_6") (pintype "passive"))
      (node (ref "IC2") (pin "29") (pinfunction "PC6(/RESET)_29") (pintype "bidirectional"))
      (node (ref "ISP1") (pin "5") (pinfunction "RST_5") (pintype "output"))
      (node (ref "R10") (pin "1") (pinfunction "1_1") (pintype "passive"))
    )
    (net (code "36") (name "/RX-I") (class "Default")
      (node (ref "FTDI") (pin "5") (pinfunction "5_5") (pintype "passive"))
      (node (ref "IC2") (pin "30") (pinfunction "PD0(RXD)_30") (pintype "bidirectional"))
      (node (ref "X2") (pin "35") (pinfunction "TXD0_35") (pintype "output"))
    )
    (net (code "37") (name "/RXD0") (class "Default")
      (node (ref "D13") (pin "A") (pinfunction "A_A") (pintype "passive"))
      (node (ref "X2") (pin "34") (pinfunction "RXD0_34") (pintype "input"))
    )
    (net (code "38") (name "/SCK") (class "Default")
      (node (ref "IC2") (pin "17") (pinfunction "PB5(SCK)_17") (pintype "bidirectional"))
      (node (ref "ISP1") (pin "3") (pinfunction "SCK_3") (pintype "output"))
    )
    (net (code "39") (name "/SCL") (class "Default")
      (node (ref "I2C") (pin "3") (pinfunction "3_3") (pintype "passive"))
      (node (ref "IC2") (pin "28") (pinfunction "PC5(ADC5/SCL)_28") (pintype "bidirectional"))
      (node (ref "IC5") (pin "12") (pinfunction "SCL_12") (pintype "input"))
      (node (ref "R12") (pin "1") (pinfunction "1_1") (pintype "passive"))
    )
    (net (code "40") (name "/SDA") (class "Default")
      (node (ref "I2C") (pin "4") (pinfunction "4_4") (pintype "passive"))
      (node (ref "IC2") (pin "27") (pinfunction "PC4(ADC4/SDA)_27") (pintype "bidirectional"))
      (node (ref "IC5") (pin "13") (pinfunction "SDA_13") (pintype "bidirectional"))
      (node (ref "R11") (pin "1") (pinfunction "1_1") (pintype "passive"))
    )
    (net (code "41") (name "/TX") (class "Default")
      (node (ref "D13") (pin "C") (pinfunction "C_C") (pintype "passive"))
      (node (ref "FTDI") (pin "4") (pinfunction "4_4") (pintype "passive"))
      (node (ref "IC2") (pin "31") (pinfunction "PD1(TXD)_31") (pintype "bidirectional"))
    )
    (net (code "42") (name "/UGND") (class "Default")
      (node (ref "C12") (pin "2") (pinfunction "2_2") (pintype "passive"))
      (node (ref "C17") (pin "-") (pinfunction "-_-") (pintype "passive"))
      (node (ref "C18") (pin "1") (pinfunction "1_1") (pintype "passive"))
      (node (ref "C19") (pin "1") (pinfunction "1_1") (pintype "passive"))
      (node (ref "C20") (pin "2") (pinfunction "2_2") (pintype "passive"))
      (node (ref "C21") (pin "2") (pinfunction "2_2") (pintype "passive"))
      (node (ref "IC2") (pin "21") (pinfunction "GND_21") (pintype "power_in"))
      (node (ref "IC2") (pin "3") (pinfunction "GND_3") (pintype "power_in"))
      (node (ref "IC2") (pin "5") (pinfunction "GND_5") (pintype "power_in"))
      (node (ref "SH1") (pin "1") (pinfunction "P$1_1") (pintype "bidirectional"))
      (node (ref "SH2") (pin "2") (pinfunction "P$2_2") (pintype "bidirectional"))
    )
    (net (code "43") (name "/VCC") (class "Default")
      (node (ref "C17") (pin "+") (pinfunction "+_+") (pintype "passive"))
      (node (ref "C18") (pin "2") (pinfunction "2_2") (pintype "passive"))
      (node (ref "C19") (pin "2") (pinfunction "2_2") (pintype "passive"))
      (node (ref "IC2") (pin "4") (pinfunction "VCC_4") (pintype "power_in"))
      (node (ref "IC2") (pin "6") (pinfunction "VCC_6") (pintype "power_in"))
      (node (ref "R27") (pin "1") (pinfunction "1_1") (pintype "passive"))
    )
    (net (code "44") (name "/WELD_DETECT") (class "Default")
      (node (ref "IC2") (pin "1") (pinfunction "PD3(INT1)_1") (pintype "bidirectional"))
      (node (ref "IC8") (pin "P$6") (pinfunction "O2_P$6") (pintype "bidirectional"))
    )
    (net (code "45") (name "3.3V") (class "Default")
      (node (ref "C22") (pin "1") (pinfunction "1_1") (pintype "passive"))
      (node (ref "C23") (pin "1") (pinfunction "1_1") (pintype "passive"))
      (node (ref "C25") (pin "1") (pinfunction "1_1") (pintype "passive"))
      (node (ref "C31") (pin "1") (pinfunction "1_1") (pintype "passive"))
      (node (ref "C34") (pin "1") (pinfunction "1_1") (pintype "passive"))
      (node (ref "JP1") (pin "2") (pinfunction "2_2") (pintype "power_in"))
      (node (ref "JP3") (pin "1") (pinfunction "1_1") (pintype "passive"))
      (node (ref "L1") (pin "P$2") (pinfunction "2_P$2") (pintype "passive"))
      (node (ref "LED1") (pin "2") (pinfunction "VDD_2") (pintype "power_in"))
      (node (ref "LED2") (pin "2") (pinfunction "VDD_2") (pintype "power_in"))
      (node (ref "R13") (pin "1") (pinfunction "1_1") (pintype "passive"))
      (node (ref "U2") (pin "1") (pinfunction "FB_1") (pintype "bidirectional"))
      (node (ref "X2") (pin "2") (pinfunction "3.3V_2") (pintype "passive"))
    )
    (net (code "46") (name "ESPSCL") (class "Default")
      (node (ref "JP1") (pin "4") (pinfunction "4_4") (pintype "passive"))
      (node (ref "X2") (pin "36") (pinfunction "IO22_36") (pintype "bidirectional"))
    )
    (net (code "47") (name "ESPSDA") (class "Default")
      (node (ref "JP1") (pin "3") (pinfunction "3_3") (pintype "passive"))
      (node (ref "X2") (pin "33") (pinfunction "IO21_33") (pintype "bidirectional"))
    )
    (net (code "48") (name "GND") (class "Default")
      (node (ref "BOOT0") (pin "A") (pinfunction "P_A") (pintype "passive"))
      (node (ref "BOOT0") (pin "A'") (pinfunction "P1_A'") (pintype "passive"))
      (node (ref "C10") (pin "2") (pinfunction "2_2") (pintype "passive"))
      (node (ref "C11") (pin "2") (pinfunction "2_2") (pintype "passive"))
      (node (ref "C14") (pin "C") (pinfunction "-_C") (pintype "passive"))
      (node (ref "C15") (pin "1") (pinfunction "1_1") (pintype "passive"))
      (node (ref "C16") (pin "1") (pinfunction "1_1") (pintype "passive"))
      (node (ref "C22") (pin "2") (pinfunction "2_2") (pintype "passive"))
      (node (ref "C23") (pin "2") (pinfunction "2_2") (pintype "passive"))
      (node (ref "C24") (pin "2") (pinfunction "2_2") (pintype "passive"))
      (node (ref "C25") (pin "2") (pinfunction "2_2") (pintype "passive"))
      (node (ref "C26") (pin "1") (pinfunction "1_1") (pintype "passive"))
      (node (ref "C27") (pin "1") (pinfunction "1_1") (pintype "passive"))
      (node (ref "C28") (pin "2") (pinfunction "2_2") (pintype "passive"))
      (node (ref "C29") (pin "2") (pinfunction "2_2") (pintype "passive"))
      (node (ref "C3") (pin "2") (pinfunction "2_2") (pintype "passive"))
      (node (ref "C31") (pin "2") (pinfunction "2_2") (pintype "passive"))
      (node (ref "C33") (pin "2") (pinfunction "2_2") (pintype "passive"))
      (node (ref "C34") (pin "2") (pinfunction "2_2") (pintype "passive"))
      (node (ref "C35") (pin "2") (pinfunction "2_2") (pintype "passive"))
      (node (ref "C36") (pin "2") (pinfunction "2_2") (pintype "passive"))
      (node (ref "C4") (pin "2") (pinfunction "2_2") (pintype "passive"))
      (node (ref "C5") (pin "2") (pinfunction "2_2") (pintype "passive"))
      (node (ref "C6") (pin "1") (pinfunction "1_1") (pintype "passive"))
      (node (ref "C8") (pin "2") (pinfunction "2_2") (pintype "passive"))
      (node (ref "C9") (pin "2") (pinfunction "2_2") (pintype "passive"))
      (node (ref "D1") (pin "1") (pinfunction "K1_1") (pintype "passive"))
      (node (ref "FTDI") (pin "1") (pinfunction "1_1") (pintype "passive"))
      (node (ref "GFCI") (pin "1") (pinfunction "1_1") (pintype "passive"))
      (node (ref "I2C") (pin "1") (pinfunction "1_1") (pintype "passive"))
      (node (ref "IC1") (pin "5") (pinfunction "+IN_5") (pintype "input"))
      (node (ref "IC3") (pin "3") (pinfunction "+IN1_3") (pintype "input"))
      (node (ref "IC3") (pin "4") (pinfunction "GND_4") (pintype "power_in"))
      (node (ref "IC4") (pin "3") (pinfunction "GND_3") (pintype "bidirectional"))
      (node (ref "IC5") (pin "10") (pinfunction "VSS_10") (pintype "power_in"))
      (node (ref "IC5") (pin "15") (pinfunction "A0_15") (pintype "input"))
      (node (ref "IC5") (pin "16") (pinfunction "A1_16") (pintype "input"))
      (node (ref "IC5") (pin "17") (pinfunction "A2_17") (pintype "input"))
      (node (ref "IC7") (pin "P$1") (pinfunction "1_P$1") (pintype "bidirectional"))
      (node (ref "IC7") (pin "P$3") (pinfunction "3_P$3") (pintype "bidirectional"))
      (node (ref "IC7") (pin "P$4") (pinfunction "4_P$4") (pintype "bidirectional"))
      (node (ref "IC8") (pin "P$5") (pinfunction "GND_P$5") (pintype "bidirectional"))
      (node (ref "ISP1") (pin "6") (pinfunction "GND_6") (pintype "power_in"))
      (node (ref "J1") (pin "1") (pinfunction "1_1") (pintype "passive"))
      (node (ref "J2") (pin "2") (pinfunction "2_2") (pintype "passive"))
      (node (ref "JP1") (pin "1") (pinfunction "1_1") (pintype "power_in"))
      (node (ref "JP3") (pin "2") (pinfunction "2_2") (pintype "passive"))
      (node (ref "JP6") (pin "2") (pinfunction "2_2") (pintype "passive"))
      (node (ref "LED1") (pin "4") (pinfunction "GND_4") (pintype "power_in"))
      (node (ref "LED2") (pin "4") (pinfunction "GND_4") (pintype "power_in"))
      (node (ref "PS1") (pin "V-") (pinfunction "V-_V-") (pintype "bidirectional"))
      (node (ref "Q2") (pin "2") (pinfunction "E_2") (pintype "passive"))
      (node (ref "R15") (pin "2") (pinfunction "2_2") (pintype "passive"))
      (node (ref "R17") (pin "1") (pinfunction "1_1") (pintype "passive"))
      (node (ref "R19") (pin "2") (pinfunction "2_2") (pintype "passive"))
      (node (ref "R21") (pin "2") (pinfunction "2_2") (pintype "passive"))
      (node (ref "R6") (pin "2") (pinfunction "2_2") (pintype "passive"))
      (node (ref "R8") (pin "1") (pinfunction "1_1") (pintype "passive"))
      (node (ref "RESET") (pin "A") (pinfunction "P_A") (pintype "passive"))
      (node (ref "RESET") (pin "A'") (pinfunction "P1_A'") (pintype "passive"))
      (node (ref "SH1") (pin "2") (pinfunction "P$2_2") (pintype "bidirectional"))
      (node (ref "TVS") (pin "A") (pinfunction "A_A") (pintype "passive"))
      (node (ref "U$17") (pin "P$2") (pinfunction "P$2_P$2") (pintype "bidirectional"))
      (node (ref "U$23") (pin "P$2") (pinfunction "P$2_P$2") (pintype "bidirectional"))
      (node (ref "U$27") (pin "P$1") (pinfunction "GND_P$1") (pintype "bidirectional"))
      (node (ref "U$9") (pin "P$1") (pinfunction "GND_P$1") (pintype "bidirectional"))
      (node (ref "U1") (pin "4") (pinfunction "GND_4") (pintype "bidirectional"))
      (node (ref "U2") (pin "4") (pinfunction "GND_4") (pintype "bidirectional"))
      (node (ref "X2") (pin "1") (pinfunction "GND_1") (pintype "passive"))
      (node (ref "X2") (pin "15") (pinfunction "GND_15") (pintype "passive"))
      (node (ref "X2") (pin "38") (pinfunction "GND_38") (pintype "passive"))
      (node (ref "X2") (pin "P$1") (pinfunction "GND_P$1") (pintype "passive"))
    )
    (net (code "49") (name "Net-(C14-+)") (class "Default")
      (node (ref "C14") (pin "A") (pinfunction "+_A") (pintype "passive"))
      (node (ref "C7") (pin "2") (pinfunction "2_2") (pintype "passive"))
      (node (ref "D3") (pin "C") (pinfunction "C_C") (pintype "passive"))
      (node (ref "R16") (pin "1") (pinfunction "1_1") (pintype "passive"))
      (node (ref "R18") (pin "2") (pinfunction "2_2") (pintype "passive"))
    )
    (net (code "50") (name "Net-(D1-AA)") (class "Default")
      (node (ref "D1") (pin "2") (pinfunction "K2_2") (pintype "passive"))
      (node (ref "D1") (pin "3") (pinfunction "AA_3") (pintype "passive"))
      (node (ref "GFCI") (pin "2") (pinfunction "2_2") (pintype "passive"))
      (node (ref "J1") (pin "2") (pinfunction "2_2") (pintype "passive"))
      (node (ref "R17") (pin "2") (pinfunction "2_2") (pintype "passive"))
      (node (ref "R20") (pin "2") (pinfunction "2_2") (pintype "passive"))
    )
    (net (code "51") (name "Net-(D7-PadA)") (class "Default")
      (node (ref "D7") (pin "A") (pinfunction "A_A") (pintype "passive"))
      (node (ref "R32") (pin "1") (pinfunction "1_1") (pintype "passive"))
    )
    (net (code "52") (name "Net-(D8-PadA)") (class "Default")
      (node (ref "D8") (pin "A") (pinfunction "A_A") (pintype "passive"))
      (node (ref "R34") (pin "1") (pinfunction "1_1") (pintype "passive"))
    )
    (net (code "53") (name "Net-(D9-PadA)") (class "Default")
      (node (ref "D9") (pin "A") (pinfunction "A_A") (pintype "passive"))
      (node (ref "R36") (pin "1") (pinfunction "1_1") (pintype "passive"))
    )
    (net (code "54") (name "Net-(D10-PadA)") (class "Default")
      (node (ref "D10") (pin "A") (pinfunction "A_A") (pintype "passive"))
      (node (ref "R38") (pin "1") (pinfunction "1_1") (pintype "passive"))
    )
    (net (code "55") (name "Net-(D11-K1)") (class "Default")
      (node (ref "AMP") (pin "1") (pinfunction "1_1") (pintype "passive"))
      (node (ref "C11") (pin "1") (pinfunction "1_1") (pintype "passive"))
      (node (ref "D11") (pin "1") (pinfunction "K1_1") (pintype "passive"))
      (node (ref "J3") (pin "1") (pinfunction "1_1") (pintype "passive"))
      (node (ref "R21") (pin "1") (pinfunction "1_1") (pintype "passive"))
      (node (ref "R25") (pin "2") (pinfunction "2_2") (pintype "passive"))
      (node (ref "R26") (pin "1") (pinfunction "1_1") (pintype "passive"))
    )
    (net (code "56") (name "Net-(IC1A--IN)") (class "Default")
      (node (ref "C15") (pin "2") (pinfunction "2_2") (pintype "passive"))
      (node (ref "IC1") (pin "2") (pinfunction "-IN_2") (pintype "input"))
      (node (ref "R8") (pin "2") (pinfunction "2_2") (pintype "passive"))
      (node (ref "R9") (pin "2") (pinfunction "2_2") (pintype "passive"))
    )
    (net (code "57") (name "Net-(IC1A-OUT)") (class "Default")
      (node (ref "IC1") (pin "1") (pinfunction "OUT_1") (pintype "output"))
      (node (ref "R1") (pin "2") (pinfunction "2_2") (pintype "passive"))
    )
    (net (code "58") (name "Net-(IC1B--IN)") (class "Default")
      (node (ref "IC1") (pin "6") (pinfunction "-IN_6") (pintype "input"))
      (node (ref "IC1") (pin "7") (pinfunction "OUT_7") (pintype "output"))
    )
    (net (code "59") (name "Net-(IC1C-P$V-)") (class "Default")
      (node (ref "C26") (pin "2") (pinfunction "2_2") (pintype "passive"))
      (node (ref "C5") (pin "1") (pinfunction "1_1") (pintype "passive"))
      (node (ref "IC1") (pin "4") (pinfunction "P$V-_4") (pintype "bidirectional"))
      (node (ref "IC4") (pin "5") (pinfunction "VOUT_5") (pintype "bidirectional"))
    )
    (net (code "60") (name "Net-(IC2-PB6(XTAL1{slash}TOSC1))") (class "Default")
      (node (ref "C1") (pin "2") (pinfunction "2_2") (pintype "passive"))
      (node (ref "IC2") (pin "7") (pinfunction "PB6(XTAL1/TOSC1)_7") (pintype "bidirectional"))
      (node (ref "Q1") (pin "2") (pinfunction "X1_2") (pintype "bidirectional"))
    )
    (net (code "61") (name "Net-(IC2-PB7(XTAL2{slash}TOSC2))") (class "Default")
      (node (ref "C2") (pin "1") (pinfunction "1_1") (pintype "passive"))
      (node (ref "IC2") (pin "8") (pinfunction "PB7(XTAL2/TOSC2)_8") (pintype "bidirectional"))
      (node (ref "Q1") (pin "4") (pinfunction "X2_4") (pintype "bidirectional"))
    )
    (net (code "62") (name "Net-(IC2-PD7(AIN1))") (class "Default")
      (node (ref "IC2") (pin "11") (pinfunction "PD7(AIN1)_11") (pintype "bidirectional"))
      (node (ref "R31") (pin "1") (pinfunction "1_1") (pintype "passive"))
    )
    (net (code "63") (name "Net-(IC3A--IN1)") (class "Default")
      (node (ref "C7") (pin "1") (pinfunction "1_1") (pintype "passive"))
      (node (ref "IC3") (pin "2") (pinfunction "-IN1_2") (pintype "input"))
      (node (ref "R16") (pin "2") (pinfunction "2_2") (pintype "passive"))
      (node (ref "R20") (pin "1") (pinfunction "1_1") (pintype "passive"))
    )
    (net (code "64") (name "Net-(IC3A-OUT1)") (class "Default")
      (node (ref "D3") (pin "A") (pinfunction "A_A") (pintype "passive"))
      (node (ref "IC3") (pin "1") (pinfunction "OUT1_1") (pintype "output"))
    )
    (net (code "65") (name "Net-(IC3B-+IN2)") (class "Default")
      (node (ref "IC3") (pin "5") (pinfunction "+IN2_5") (pintype "input"))
      (node (ref "R18") (pin "1") (pinfunction "1_1") (pintype "passive"))
    )
    (net (code "66") (name "Net-(IC3B--IN2)") (class "Default")
      (node (ref "C16") (pin "2") (pinfunction "2_2") (pintype "passive"))
      (node (ref "IC3") (pin "6") (pinfunction "-IN2_6") (pintype "input"))
      (node (ref "R14") (pin "2") (pinfunction "2_2") (pintype "passive"))
      (node (ref "R15") (pin "1") (pinfunction "1_1") (pintype "passive"))
    )
    (net (code "67") (name "Net-(IC3B-OUT2)") (class "Default")
      (node (ref "D4") (pin "A") (pinfunction "A_A") (pintype "passive"))
      (node (ref "IC3") (pin "7") (pinfunction "OUT2_7") (pintype "output"))
    )
    (net (code "68") (name "Net-(IC4-CAP+)") (class "Default")
      (node (ref "C13") (pin "2") (pinfunction "2_2") (pintype "passive"))
      (node (ref "IC4") (pin "2") (pinfunction "CAP+_2") (pintype "bidirectional"))
    )
    (net (code "69") (name "Net-(IC4-CAP-)") (class "Default")
      (node (ref "C13") (pin "1") (pinfunction "1_1") (pintype "passive"))
      (node (ref "IC4") (pin "4") (pinfunction "CAP-_4") (pintype "bidirectional"))
    )
    (net (code "70") (name "Net-(IC7-2)") (class "Default")
      (node (ref "IC7") (pin "P$2") (pinfunction "2_P$2") (pintype "bidirectional"))
      (node (ref "R29") (pin "1") (pinfunction "1_1") (pintype "passive"))
    )
    (net (code "71") (name "Net-(IC8-I1+)") (class "Default")
      (node (ref "D7") (pin "C") (pinfunction "C_C") (pintype "passive"))
      (node (ref "D8") (pin "C") (pinfunction "C_C") (pintype "passive"))
      (node (ref "IC8") (pin "P$1") (pinfunction "I1+_P$1") (pintype "bidirectional"))
    )
    (net (code "72") (name "Net-(IC8-I2+)") (class "Default")
      (node (ref "D10") (pin "C") (pinfunction "C_C") (pintype "passive"))
      (node (ref "D9") (pin "C") (pinfunction "C_C") (pintype "passive"))
      (node (ref "IC8") (pin "P$4") (pinfunction "I2+_P$4") (pintype "bidirectional"))
    )
    (net (code "73") (name "Net-(J2-Pad1)") (class "Default")
      (node (ref "J2") (pin "1") (pinfunction "1_1") (pintype "passive"))
      (node (ref "R23") (pin "2") (pinfunction "2_2") (pintype "passive"))
      (node (ref "U$17") (pin "P$1") (pinfunction "P$1_P$1") (pintype "bidirectional"))
      (node (ref "U$23") (pin "P$1") (pinfunction "P$1_P$1") (pintype "bidirectional"))
    )
    (net (code "74") (name "Net-(L1-1)") (class "Default")
      (node (ref "C30") (pin "2") (pinfunction "2_2") (pintype "passive"))
      (node (ref "L1") (pin "P$1") (pinfunction "1_P$1") (pintype "passive"))
      (node (ref "U2") (pin "5") (pinfunction "SW_5") (pintype "bidirectional"))
    )
    (net (code "75") (name "Net-(L2-1)") (class "Default")
      (node (ref "C32") (pin "2") (pinfunction "2_2") (pintype "passive"))
      (node (ref "L2") (pin "P$1") (pinfunction "1_P$1") (pintype "passive"))
      (node (ref "U1") (pin "5") (pinfunction "SW_5") (pintype "bidirectional"))
    )
    (net (code "76") (name "Net-(L3-Pad2)") (class "Default")
      (node (ref "L3") (pin "2") (pinfunction "2_2") (pintype "passive"))
      (node (ref "R27") (pin "2") (pinfunction "2_2") (pintype "passive"))
    )
    (net (code "77") (name "Net-(LED1-DO)") (class "Default")
      (node (ref "LED1") (pin "3") (pinfunction "DO_3") (pintype "output"))
      (node (ref "LED2") (pin "1") (pinfunction "DI_1") (pintype "input"))
    )
    (net (code "78") (name "Net-(Q1-G1)") (class "Default")
      (node (ref "C1") (pin "1") (pinfunction "1_1") (pintype "passive"))
      (node (ref "C2") (pin "2") (pinfunction "2_2") (pintype "passive"))
      (node (ref "Q1") (pin "1") (pinfunction "G1_1") (pintype "power_in"))
      (node (ref "Q1") (pin "3") (pinfunction "G2_3") (pintype "power_in"))
      (node (ref "SH2") (pin "1") (pinfunction "P$1_1") (pintype "bidirectional"))
    )
    (net (code "79") (name "Net-(Q2-B)") (class "Default")
      (node (ref "Q2") (pin "1") (pinfunction "B_1") (pintype "passive"))
      (node (ref "R24") (pin "1") (pinfunction "1_1") (pintype "passive"))
    )
    (net (code "80") (name "Net-(Q2-C)") (class "Default")
      (node (ref "D5") (pin "A") (pinfunction "A_A") (pintype "passive"))
      (node (ref "JP7") (pin "1") (pinfunction "1_1") (pintype "passive"))
      (node (ref "Q2") (pin "3") (pinfunction "C_3") (pintype "passive"))
      (node (ref "U$20") (pin "P$2") (pinfunction "P$2_P$2") (pintype "bidirectional"))
    )
    (net (code "81") (name "Net-(R32-Pad2)") (class "Default")
      (node (ref "R32") (pin "2") (pinfunction "2_2") (pintype "passive"))
      (node (ref "R33") (pin "1") (pinfunction "1_1") (pintype "passive"))
    )
    (net (code "82") (name "Net-(R34-Pad2)") (class "Default")
      (node (ref "R34") (pin "2") (pinfunction "2_2") (pintype "passive"))
      (node (ref "R35") (pin "1") (pinfunction "1_1") (pintype "passive"))
    )
    (net (code "83") (name "Net-(R36-Pad2)") (class "Default")
      (node (ref "R36") (pin "2") (pinfunction "2_2") (pintype "passive"))
      (node (ref "R37") (pin "1") (pinfunction "1_1") (pintype "passive"))
    )
    (net (code "84") (name "Net-(R38-Pad2)") (class "Default")
      (node (ref "R38") (pin "2") (pinfunction "2_2") (pintype "passive"))
      (node (ref "R39") (pin "1") (pinfunction "1_1") (pintype "passive"))
    )
    (net (code "85") (name "Net-(U$24-1)") (class "Default")
      (node (ref "R4") (pin "1") (pinfunction "1_1") (pintype "passive"))
      (node (ref "RGB_LED") (pin "4") (pinfunction "4_4") (pintype "passive"))
      (node (ref "U$24") (pin "P$1") (pinfunction "1_P$1") (pintype "bidirectional"))
    )
    (net (code "86") (name "Net-(U$24-2)") (class "Default")
      (node (ref "R3") (pin "1") (pinfunction "1_1") (pintype "passive"))
      (node (ref "RGB_LED") (pin "3") (pinfunction "3_3") (pintype "passive"))
      (node (ref "U$24") (pin "P$2") (pinfunction "2_P$2") (pintype "bidirectional"))
    )
    (net (code "87") (name "Net-(U$24-3)") (class "Default")
      (node (ref "R2") (pin "1") (pinfunction "1_1") (pintype "passive"))
      (node (ref "RGB_LED") (pin "2") (pinfunction "2_2") (pintype "passive"))
      (node (ref "U$24") (pin "P$3") (pinfunction "3_P$3") (pintype "bidirectional"))
    )
    (net (code "88") (name "Net-(U1-BST)") (class "Default")
      (node (ref "C32") (pin "1") (pinfunction "1_1") (pintype "passive"))
      (node (ref "U1") (pin "6") (pinfunction "BST_6") (pintype "bidirectional"))
    )
    (net (code "89") (name "Net-(U2-BST)") (class "Default")
      (node (ref "C30") (pin "1") (pinfunction "1_1") (pintype "passive"))
      (node (ref "U2") (pin "6") (pinfunction "BST_6") (pintype "bidirectional"))
    )
    (net (code "90") (name "PE") (class "Default")
      (node (ref "C37") (pin "P$1") (pinfunction "1_P$1") (pintype "passive"))
      (node (ref "C38") (pin "P$1") (pinfunction "1_P$1") (pintype "passive"))
      (node (ref "G1") (pin "1") (pinfunction "1_1") (pintype "passive"))
      (node (ref "IC8") (pin "P$2") (pinfunction "I1-_P$2") (pintype "bidirectional"))
      (node (ref "IC8") (pin "P$3") (pinfunction "I2-_P$3") (pintype "bidirectional"))
      (node (ref "M3") (pin "P$1") (pinfunction "1_P$1") (pintype "passive"))
      (node (ref "M4") (pin "P$1") (pinfunction "1_P$1") (pintype "passive"))
      (node (ref "U$3") (pin "P$1") (pinfunction "GND_P$1") (pintype "bidirectional"))
    )
    (net (code "91") (name "unconnected-(D11-AA-Pad3)") (class "Default")
      (node (ref "D11") (pin "3") (pinfunction "AA_3") (pintype "passive"))
    )
    (net (code "92") (name "unconnected-(FTDI-Pad2)") (class "Default")
      (node (ref "FTDI") (pin "2") (pinfunction "2_2") (pintype "passive"))
    )
    (net (code "93") (name "unconnected-(IC4-LV-Pad6)") (class "Default")
      (node (ref "IC4") (pin "6") (pinfunction "LV_6") (pintype "bidirectional"))
    )
    (net (code "94") (name "unconnected-(IC4-OSC-Pad7)") (class "Default")
      (node (ref "IC4") (pin "7") (pinfunction "OSC_7") (pintype "bidirectional"))
    )
    (net (code "95") (name "unconnected-(IC5-GPA0-Pad21)") (class "Default")
      (node (ref "IC5") (pin "21") (pinfunction "GPA0_21") (pintype "bidirectional"))
    )
    (net (code "96") (name "unconnected-(IC5-GPA1-Pad22)") (class "Default")
      (node (ref "IC5") (pin "22") (pinfunction "GPA1_22") (pintype "bidirectional"))
    )
    (net (code "97") (name "unconnected-(IC5-GPA2-Pad23)") (class "Default")
      (node (ref "IC5") (pin "23") (pinfunction "GPA2_23") (pintype "bidirectional"))
    )
    (net (code "98") (name "unconnected-(IC5-GPA3-Pad24)") (class "Default")
      (node (ref "IC5") (pin "24") (pinfunction "GPA3_24") (pintype "bidirectional"))
    )
    (net (code "99") (name "unconnected-(IC5-GPA4-Pad25)") (class "Default")
      (node (ref "IC5") (pin "25") (pinfunction "GPA4_25") (pintype "bidirectional"))
    )
    (net (code "100") (name "unconnected-(IC5-GPA5-Pad26)") (class "Default")
      (node (ref "IC5") (pin "26") (pinfunction "GPA5_26") (pintype "bidirectional"))
    )
    (net (code "101") (name "unconnected-(IC5-GPB1-Pad2)") (class "Default")
      (node (ref "IC5") (pin "2") (pinfunction "GPB1_2") (pintype "bidirectional"))
    )
    (net (code "102") (name "unconnected-(IC5-GPB2-Pad3)") (class "Default")
      (node (ref "IC5") (pin "3") (pinfunction "GPB2_3") (pintype "bidirectional"))
    )
    (net (code "103") (name "unconnected-(IC5-GPB3-Pad4)") (class "Default")
      (node (ref "IC5") (pin "4") (pinfunction "GPB3_4") (pintype "bidirectional"))
    )
    (net (code "104") (name "unconnected-(IC5-GPB4-Pad5)") (class "Default")
      (node (ref "IC5") (pin "5") (pinfunction "GPB4_5") (pintype "bidirectional"))
    )
    (net (code "105") (name "unconnected-(IC5-GPB5-Pad6)") (class "Default")
      (node (ref "IC5") (pin "6") (pinfunction "GPB5_6") (pintype "bidirectional"))
    )
    (net (code "106") (name "unconnected-(IC5-GPB6-Pad7)") (class "Default")
      (node (ref "IC5") (pin "7") (pinfunction "GPB6_7") (pintype "bidirectional"))
    )
    (net (code "107") (name "unconnected-(IC5-GPB7-Pad8)") (class "Default")
      (node (ref "IC5") (pin "8") (pinfunction "GPB7_8") (pintype "bidirectional"))
    )
    (net (code "108") (name "unconnected-(IC5-INTA-Pad20)") (class "Default")
      (node (ref "IC5") (pin "20") (pinfunction "INTA_20") (pintype "output"))
    )
    (net (code "109") (name "unconnected-(IC5-INTB-Pad19)") (class "Default")
      (node (ref "IC5") (pin "19") (pinfunction "INTB_19") (pintype "output"))
    )
    (net (code "110") (name "unconnected-(IC7-5-PadP$5)") (class "Default")
      (node (ref "IC7") (pin "P$5") (pinfunction "5_P$5") (pintype "bidirectional"))
    )
    (net (code "111") (name "unconnected-(U$22-PadP$1)") (class "Default")
      (node (ref "U$22") (pin "P$1") (pinfunction "P$1_P$1") (pintype "bidirectional"))
    )
    (net (code "112") (name "unconnected-(U$25-1-PadP$1)") (class "Default")
      (node (ref "U$25") (pin "P$1") (pinfunction "1_P$1") (pintype "passive"))
    )
    (net (code "113") (name "unconnected-(U$25-2-PadP$2)") (class "Default")
      (node (ref "U$25") (pin "P$2") (pinfunction "2_P$2") (pintype "passive"))
    )
    (net (code "114") (name "unconnected-(U$25-4-PadP$4)") (class "Default")
      (node (ref "U$25") (pin "P$4") (pinfunction "4_P$4") (pintype "passive"))
    )
    (net (code "115") (name "unconnected-(X2-CLK-Pad20)") (class "Default")
      (node (ref "X2") (pin "20") (pinfunction "CLK_20") (pintype "bidirectional"))
    )
    (net (code "116") (name "unconnected-(X2-CMD-Pad19)") (class "Default")
      (node (ref "X2") (pin "19") (pinfunction "CMD_19") (pintype "bidirectional"))
    )
    (net (code "117") (name "unconnected-(X2-I34{slash}A1_6-Pad6)") (class "Default")
      (node (ref "X2") (pin "6") (pinfunction "I34/A1_6_6") (pintype "bidirectional"))
    )
    (net (code "118") (name "unconnected-(X2-I35{slash}A1_7-Pad7)") (class "Default")
      (node (ref "X2") (pin "7") (pinfunction "I35/A1_7_7") (pintype "bidirectional"))
    )
    (net (code "119") (name "unconnected-(X2-IO2{slash}A2_2-Pad24)") (class "Default")
      (node (ref "X2") (pin "24") (pinfunction "IO2/A2_2_24") (pintype "bidirectional"))
    )
    (net (code "120") (name "unconnected-(X2-IO4{slash}A2_0-Pad26)") (class "Default")
      (node (ref "X2") (pin "26") (pinfunction "IO4/A2_0_26") (pintype "bidirectional"))
    )
    (net (code "121") (name "unconnected-(X2-IO5-Pad29)") (class "Default")
      (node (ref "X2") (pin "29") (pinfunction "IO5_29") (pintype "bidirectional"))
    )
    (net (code "122") (name "unconnected-(X2-IO12{slash}A2_5-Pad14)") (class "Default")
      (node (ref "X2") (pin "14") (pinfunction "IO12/A2_5_14") (pintype "bidirectional"))
    )
    (net (code "123") (name "unconnected-(X2-IO13{slash}A2_4-Pad16)") (class "Default")
      (node (ref "X2") (pin "16") (pinfunction "IO13/A2_4_16") (pintype "bidirectional"))
    )
    (net (code "124") (name "unconnected-(X2-IO14{slash}A2_6-Pad13)") (class "Default")
      (node (ref "X2") (pin "13") (pinfunction "IO14/A2_6_13") (pintype "bidirectional"))
    )
    (net (code "125") (name "unconnected-(X2-IO15{slash}A2_3-Pad23)") (class "Default")
      (node (ref "X2") (pin "23") (pinfunction "IO15/A2_3_23") (pintype "bidirectional"))
    )
    (net (code "126") (name "unconnected-(X2-IO16-Pad27)") (class "Default")
      (node (ref "X2") (pin "27") (pinfunction "IO16_27") (pintype "bidirectional"))
    )
    (net (code "127") (name "unconnected-(X2-IO18-Pad30)") (class "Default")
      (node (ref "X2") (pin "30") (pinfunction "IO18_30") (pintype "bidirectional"))
    )
    (net (code "128") (name "unconnected-(X2-IO19-Pad31)") (class "Default")
      (node (ref "X2") (pin "31") (pinfunction "IO19_31") (pintype "bidirectional"))
    )
    (net (code "129") (name "unconnected-(X2-IO23-Pad37)") (class "Default")
      (node (ref "X2") (pin "37") (pinfunction "IO23_37") (pintype "bidirectional"))
    )
    (net (code "130") (name "unconnected-(X2-IO25{slash}DAC1{slash}A2_8-Pad10)") (class "Default")
      (node (ref "X2") (pin "10") (pinfunction "IO25/DAC1/A2_8_10") (pintype "bidirectional"))
    )
    (net (code "131") (name "unconnected-(X2-IO26{slash}DAC2{slash}A2_9-Pad11)") (class "Default")
      (node (ref "X2") (pin "11") (pinfunction "IO26/DAC2/A2_9_11") (pintype "bidirectional"))
    )
    (net (code "132") (name "unconnected-(X2-IO27{slash}A2_7-Pad12)") (class "Default")
      (node (ref "X2") (pin "12") (pinfunction "IO27/A2_7_12") (pintype "bidirectional"))
    )
    (net (code "133") (name "unconnected-(X2-IO32{slash}A1_4{slash}X32P-Pad8)") (class "Default")
      (node (ref "X2") (pin "8") (pinfunction "IO32/A1_4/X32P_8") (pintype "bidirectional"))
    )
    (net (code "134") (name "unconnected-(X2-IO33{slash}A1_5{slash}X32N-Pad9)") (class "Default")
      (node (ref "X2") (pin "9") (pinfunction "IO33/A1_5/X32N_9") (pintype "bidirectional"))
    )
    (net (code "135") (name "unconnected-(X2-IO36{slash}SEN_VP{slash}A1_0-Pad4)") (class "Default")
      (node (ref "X2") (pin "4") (pinfunction "IO36/SEN_VP/A1_0_4") (pintype "passive"))
    )
    (net (code "136") (name "unconnected-(X2-IO39{slash}SEN_VN{slash}A1_3-Pad5)") (class "Default")
      (node (ref "X2") (pin "5") (pinfunction "IO39/SEN_VN/A1_3_5") (pintype "passive"))
    )
    (net (code "137") (name "unconnected-(X2-SD0-Pad21)") (class "Default")
      (node (ref "X2") (pin "21") (pinfunction "SD0_21") (pintype "bidirectional"))
    )
    (net (code "138") (name "unconnected-(X2-SD1-Pad22)") (class "Default")
      (node (ref "X2") (pin "22") (pinfunction "SD1_22") (pintype "bidirectional"))
    )
    (net (code "139") (name "unconnected-(X2-SD2-Pad17)") (class "Default")
      (node (ref "X2") (pin "17") (pinfunction "SD2_17") (pintype "bidirectional"))
    )
    (net (code "140") (name "unconnected-(X2-SD3-Pad18)") (class "Default")
      (node (ref "X2") (pin "18") (pinfunction "SD3_18") (pintype "bidirectional"))
    )
  )
)
